# Power_Board_V3.net
KiCad netlist of a schematic drawn in EAGLE
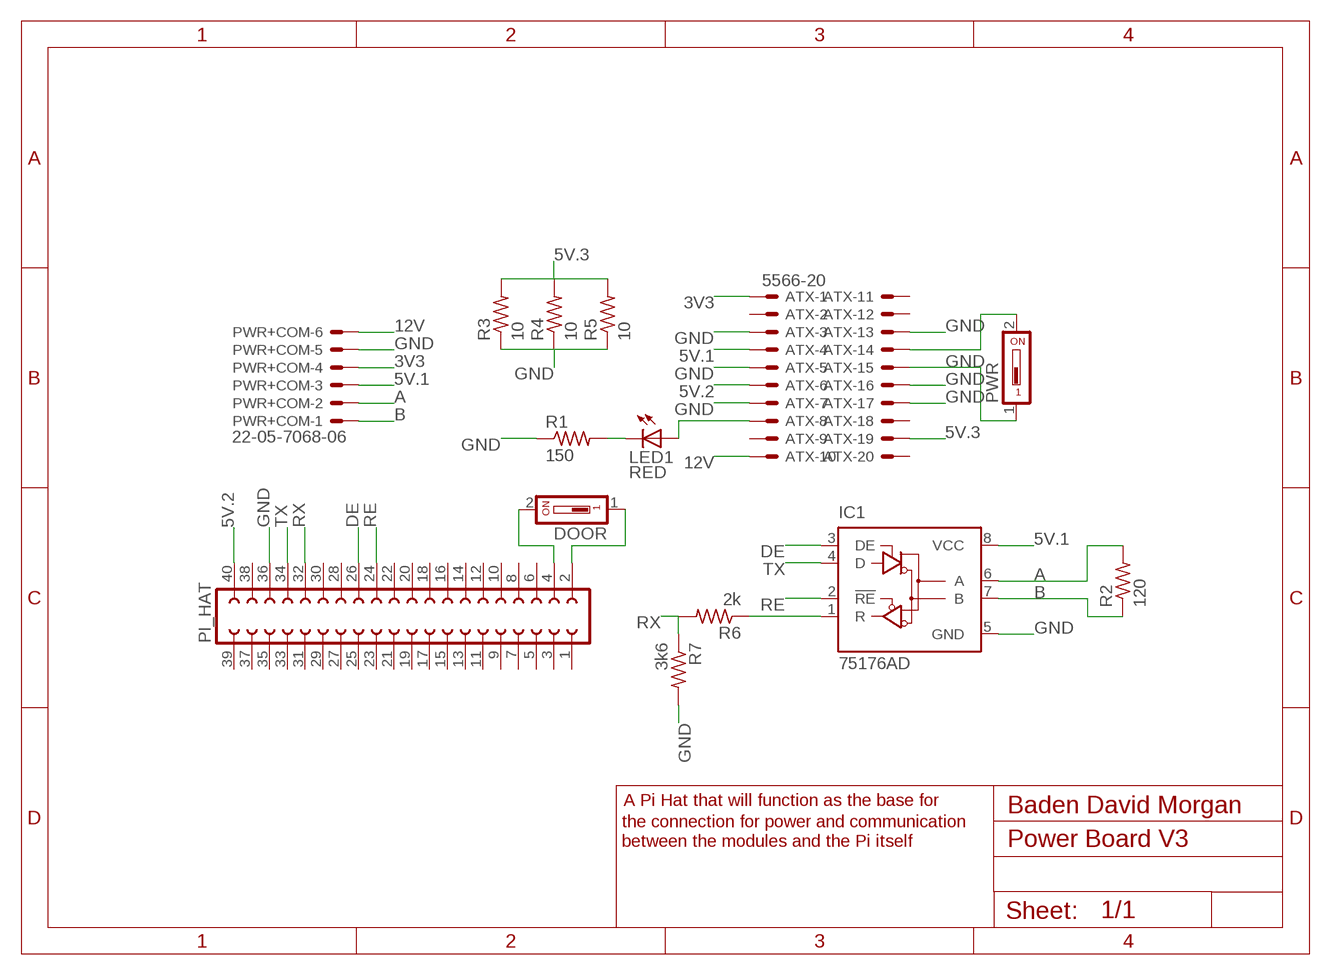
[diagram p0: schematic, sheet 1]

(export (version "E")
  (design (tool "Eeschema 10.0.6"))
  (components
    (comp (ref "ATX")
      (value "5566-20")
      (footprint "eagle-import:5566-20")
      (libsource (lib "eagle-import") (part "5566-20"))
    )
    (comp (ref "DOOR")
      (value "SD4-01")
      (footprint "eagle-import:SD4-01")
      (libsource (lib "eagle-import") (part "SD4-01"))
    )
    (comp (ref "IC1")
      (value "75176AD")
      (footprint "eagle-import:D_R-PDSO-G8")
      (libsource (lib "eagle-import") (part "75176AD"))
    )
    (comp (ref "LED1")
      (value "RED")
      (footprint "eagle-import:CHIPLED_1206")
      (libsource (lib "eagle-import") (part "LEDCHIPLED_1206"))
    )
    (comp (ref "PI_HAT")
      (value "FE20-2")
      (footprint "eagle-import:FE20-2")
      (libsource (lib "eagle-import") (part "FE20-2"))
    )
    (comp (ref "PWR")
      (value "SD4-01")
      (footprint "eagle-import:SD4-01")
      (libsource (lib "eagle-import") (part "SD4-01"))
    )
    (comp (ref "PWR+COM")
      (value "22-05-7068-06")
      (footprint "eagle-import:7395-06")
      (libsource (lib "eagle-import") (part "22-?-0605-7068"))
    )
    (comp (ref "R1")
      (value "150")
      (footprint "eagle-import:R0805")
      (libsource (lib "eagle-import") (part "resistor_R-US_R0805"))
    )
    (comp (ref "R2")
      (value "120")
      (footprint "eagle-import:R0805")
      (libsource (lib "eagle-import") (part "resistor_R-US_R0805"))
    )
    (comp (ref "R3")
      (value "10")
      (footprint "eagle-import:P0817V")
      (libsource (lib "eagle-import") (part "R-US_0817/7V"))
    )
    (comp (ref "R4")
      (value "10")
      (footprint "eagle-import:P0817V")
      (libsource (lib "eagle-import") (part "R-US_0817/7V"))
    )
    (comp (ref "R5")
      (value "10")
      (footprint "eagle-import:P0817V")
      (libsource (lib "eagle-import") (part "R-US_0817/7V"))
    )
    (comp (ref "R6")
      (value "2k")
      (footprint "eagle-import:R0805")
      (libsource (lib "eagle-import") (part "resistor_R-US_R0805"))
    )
    (comp (ref "R7")
      (value "3k6")
      (footprint "eagle-import:R0805")
      (libsource (lib "eagle-import") (part "resistor_R-US_R0805"))
    )
  )
  (nets
    (net (code "1") (name "/3V3") (class "Default")
      (node (ref "ATX") (pin "1") (pinfunction "S_1") (pintype "passive"))
      (node (ref "PWR+COM") (pin "4") (pinfunction "S_4") (pintype "passive"))
    )
    (net (code "2") (name "/5V.1") (class "Default")
      (node (ref "ATX") (pin "4") (pinfunction "S_4") (pintype "passive"))
      (node (ref "IC1") (pin "8") (pinfunction "VCC_8") (pintype "power_in"))
      (node (ref "PWR+COM") (pin "3") (pinfunction "S_3") (pintype "passive"))
    )
    (net (code "3") (name "/5V.2") (class "Default")
      (node (ref "ATX") (pin "6") (pinfunction "S_6") (pintype "passive"))
      (node (ref "PI_HAT") (pin "40") (pinfunction "40_40") (pintype "passive"))
    )
    (net (code "4") (name "/5V.3") (class "Default")
      (node (ref "ATX") (pin "19") (pinfunction "S_19") (pintype "passive"))
      (node (ref "R3") (pin "2") (pinfunction "2_2") (pintype "passive"))
      (node (ref "R4") (pin "2") (pinfunction "2_2") (pintype "passive"))
      (node (ref "R5") (pin "2") (pinfunction "2_2") (pintype "passive"))
    )
    (net (code "5") (name "/12V") (class "Default")
      (node (ref "ATX") (pin "10") (pinfunction "S_10") (pintype "passive"))
      (node (ref "PWR+COM") (pin "6") (pinfunction "S_6") (pintype "passive"))
    )
    (net (code "6") (name "/A") (class "Default")
      (node (ref "IC1") (pin "6") (pinfunction "A_6") (pintype "output"))
      (node (ref "PWR+COM") (pin "2") (pinfunction "S_2") (pintype "passive"))
      (node (ref "R2") (pin "2") (pinfunction "2_2") (pintype "passive"))
    )
    (net (code "7") (name "/B") (class "Default")
      (node (ref "IC1") (pin "7") (pinfunction "B_7") (pintype "output"))
      (node (ref "PWR+COM") (pin "1") (pinfunction "S_1") (pintype "passive"))
      (node (ref "R2") (pin "1") (pinfunction "1_1") (pintype "passive"))
    )
    (net (code "8") (name "/DE") (class "Default")
      (node (ref "IC1") (pin "3") (pinfunction "DE_3") (pintype "input"))
      (node (ref "PI_HAT") (pin "26") (pinfunction "26_26") (pintype "passive"))
    )
    (net (code "9") (name "/GND") (class "Default")
      (node (ref "ATX") (pin "13") (pinfunction "S_13") (pintype "passive"))
      (node (ref "ATX") (pin "15") (pinfunction "S_15") (pintype "passive"))
      (node (ref "ATX") (pin "16") (pinfunction "S_16") (pintype "passive"))
      (node (ref "ATX") (pin "17") (pinfunction "S_17") (pintype "passive"))
      (node (ref "ATX") (pin "3") (pinfunction "S_3") (pintype "passive"))
      (node (ref "ATX") (pin "5") (pinfunction "S_5") (pintype "passive"))
      (node (ref "ATX") (pin "7") (pinfunction "S_7") (pintype "passive"))
      (node (ref "IC1") (pin "5") (pinfunction "GND_5") (pintype "power_in"))
      (node (ref "PI_HAT") (pin "36") (pinfunction "36_36") (pintype "passive"))
      (node (ref "PWR") (pin "1") (pinfunction "1_1") (pintype "passive"))
      (node (ref "PWR+COM") (pin "5") (pinfunction "S_5") (pintype "passive"))
      (node (ref "R1") (pin "1") (pinfunction "1_1") (pintype "passive"))
      (node (ref "R3") (pin "1") (pinfunction "1_1") (pintype "passive"))
      (node (ref "R4") (pin "1") (pinfunction "1_1") (pintype "passive"))
      (node (ref "R5") (pin "1") (pinfunction "1_1") (pintype "passive"))
      (node (ref "R7") (pin "2") (pinfunction "2_2") (pintype "passive"))
    )
    (net (code "10") (name "/RE") (class "Default")
      (node (ref "IC1") (pin "2") (pinfunction "~{RE}_2") (pintype "input"))
      (node (ref "PI_HAT") (pin "24") (pinfunction "24_24") (pintype "passive"))
    )
    (net (code "11") (name "/RX") (class "Default")
      (node (ref "PI_HAT") (pin "32") (pinfunction "32_32") (pintype "passive"))
      (node (ref "R6") (pin "2") (pinfunction "2_2") (pintype "passive"))
      (node (ref "R7") (pin "1") (pinfunction "1_1") (pintype "passive"))
    )
    (net (code "12") (name "/TX") (class "Default")
      (node (ref "IC1") (pin "4") (pinfunction "D_4") (pintype "input"))
      (node (ref "PI_HAT") (pin "34") (pinfunction "34_34") (pintype "passive"))
    )
    (net (code "13") (name "Net-(ATXF-S)") (class "Default")
      (node (ref "ATX") (pin "14") (pinfunction "S_14") (pintype "passive"))
      (node (ref "PWR") (pin "2") (pinfunction "2_2") (pintype "passive"))
    )
    (net (code "14") (name "Net-(ATXS-S)") (class "Default")
      (node (ref "ATX") (pin "8") (pinfunction "S_8") (pintype "passive"))
      (node (ref "LED1") (pin "A") (pinfunction "A_A") (pintype "passive"))
    )
    (net (code "15") (name "Net-(DOOR-Pad1)") (class "Default")
      (node (ref "DOOR") (pin "1") (pinfunction "1_1") (pintype "passive"))
      (node (ref "PI_HAT") (pin "2") (pinfunction "2_2") (pintype "passive"))
    )
    (net (code "16") (name "Net-(DOOR-Pad2)") (class "Default")
      (node (ref "DOOR") (pin "2") (pinfunction "2_2") (pintype "passive"))
      (node (ref "PI_HAT") (pin "4") (pinfunction "4_4") (pintype "passive"))
    )
    (net (code "17") (name "Net-(IC1-R)") (class "Default")
      (node (ref "IC1") (pin "1") (pinfunction "R_1") (pintype "input"))
      (node (ref "R6") (pin "1") (pinfunction "1_1") (pintype "passive"))
    )
    (net (code "18") (name "Net-(LED1-PadC)") (class "Default")
      (node (ref "LED1") (pin "C") (pinfunction "C_C") (pintype "passive"))
      (node (ref "R1") (pin "2") (pinfunction "2_2") (pintype "passive"))
    )
    (net (code "19") (name "unconnected-(ATXC-S-Pad11)") (class "Default")
      (node (ref "ATX") (pin "11") (pinfunction "S_11") (pintype "passive"))
    )
    (net (code "20") (name "unconnected-(ATXD-S-Pad12)") (class "Default")
      (node (ref "ATX") (pin "12") (pinfunction "S_12") (pintype "passive"))
    )
    (net (code "21") (name "unconnected-(ATXJ-S-Pad18)") (class "Default")
      (node (ref "ATX") (pin "18") (pinfunction "S_18") (pintype "passive"))
    )
    (net (code "22") (name "unconnected-(ATXL-S-Pad2)") (class "Default")
      (node (ref "ATX") (pin "2") (pinfunction "S_2") (pintype "passive"))
    )
    (net (code "23") (name "unconnected-(ATXM-S-Pad20)") (class "Default")
      (node (ref "ATX") (pin "20") (pinfunction "S_20") (pintype "passive"))
    )
    (net (code "24") (name "unconnected-(ATXT-S-Pad9)") (class "Default")
      (node (ref "ATX") (pin "9") (pinfunction "S_9") (pintype "passive"))
    )
    (net (code "25") (name "unconnected-(PI_HAT-Pad1)") (class "Default")
      (node (ref "PI_HAT") (pin "1") (pinfunction "1_1") (pintype "passive"))
    )
    (net (code "26") (name "unconnected-(PI_HAT-Pad3)") (class "Default")
      (node (ref "PI_HAT") (pin "3") (pinfunction "3_3") (pintype "passive"))
    )
    (net (code "27") (name "unconnected-(PI_HAT-Pad5)") (class "Default")
      (node (ref "PI_HAT") (pin "5") (pinfunction "5_5") (pintype "passive"))
    )
    (net (code "28") (name "unconnected-(PI_HAT-Pad6)") (class "Default")
      (node (ref "PI_HAT") (pin "6") (pinfunction "6_6") (pintype "passive"))
    )
    (net (code "29") (name "unconnected-(PI_HAT-Pad7)") (class "Default")
      (node (ref "PI_HAT") (pin "7") (pinfunction "7_7") (pintype "passive"))
    )
    (net (code "30") (name "unconnected-(PI_HAT-Pad8)") (class "Default")
      (node (ref "PI_HAT") (pin "8") (pinfunction "8_8") (pintype "passive"))
    )
    (net (code "31") (name "unconnected-(PI_HAT-Pad9)") (class "Default")
      (node (ref "PI_HAT") (pin "9") (pinfunction "9_9") (pintype "passive"))
    )
    (net (code "32") (name "unconnected-(PI_HAT-Pad10)") (class "Default")
      (node (ref "PI_HAT") (pin "10") (pinfunction "10_10") (pintype "passive"))
    )
    (net (code "33") (name "unconnected-(PI_HAT-Pad11)") (class "Default")
      (node (ref "PI_HAT") (pin "11") (pinfunction "11_11") (pintype "passive"))
    )
    (net (code "34") (name "unconnected-(PI_HAT-Pad12)") (class "Default")
      (node (ref "PI_HAT") (pin "12") (pinfunction "12_12") (pintype "passive"))
    )
    (net (code "35") (name "unconnected-(PI_HAT-Pad13)") (class "Default")
      (node (ref "PI_HAT") (pin "13") (pinfunction "13_13") (pintype "passive"))
    )
    (net (code "36") (name "unconnected-(PI_HAT-Pad14)") (class "Default")
      (node (ref "PI_HAT") (pin "14") (pinfunction "14_14") (pintype "passive"))
    )
    (net (code "37") (name "unconnected-(PI_HAT-Pad15)") (class "Default")
      (node (ref "PI_HAT") (pin "15") (pinfunction "15_15") (pintype "passive"))
    )
    (net (code "38") (name "unconnected-(PI_HAT-Pad16)") (class "Default")
      (node (ref "PI_HAT") (pin "16") (pinfunction "16_16") (pintype "passive"))
    )
    (net (code "39") (name "unconnected-(PI_HAT-Pad17)") (class "Default")
      (node (ref "PI_HAT") (pin "17") (pinfunction "17_17") (pintype "passive"))
    )
    (net (code "40") (name "unconnected-(PI_HAT-Pad18)") (class "Default")
      (node (ref "PI_HAT") (pin "18") (pinfunction "18_18") (pintype "passive"))
    )
    (net (code "41") (name "unconnected-(PI_HAT-Pad19)") (class "Default")
      (node (ref "PI_HAT") (pin "19") (pinfunction "19_19") (pintype "passive"))
    )
    (net (code "42") (name "unconnected-(PI_HAT-Pad20)") (class "Default")
      (node (ref "PI_HAT") (pin "20") (pinfunction "20_20") (pintype "passive"))
    )
    (net (code "43") (name "unconnected-(PI_HAT-Pad21)") (class "Default")
      (node (ref "PI_HAT") (pin "21") (pinfunction "21_21") (pintype "passive"))
    )
    (net (code "44") (name "unconnected-(PI_HAT-Pad22)") (class "Default")
      (node (ref "PI_HAT") (pin "22") (pinfunction "22_22") (pintype "passive"))
    )
    (net (code "45") (name "unconnected-(PI_HAT-Pad23)") (class "Default")
      (node (ref "PI_HAT") (pin "23") (pinfunction "23_23") (pintype "passive"))
    )
    (net (code "46") (name "unconnected-(PI_HAT-Pad25)") (class "Default")
      (node (ref "PI_HAT") (pin "25") (pinfunction "25_25") (pintype "passive"))
    )
    (net (code "47") (name "unconnected-(PI_HAT-Pad27)") (class "Default")
      (node (ref "PI_HAT") (pin "27") (pinfunction "27_27") (pintype "passive"))
    )
    (net (code "48") (name "unconnected-(PI_HAT-Pad28)") (class "Default")
      (node (ref "PI_HAT") (pin "28") (pinfunction "28_28") (pintype "passive"))
    )
    (net (code "49") (name "unconnected-(PI_HAT-Pad29)") (class "Default")
      (node (ref "PI_HAT") (pin "29") (pinfunction "29_29") (pintype "passive"))
    )
    (net (code "50") (name "unconnected-(PI_HAT-Pad30)") (class "Default")
      (node (ref "PI_HAT") (pin "30") (pinfunction "30_30") (pintype "passive"))
    )
    (net (code "51") (name "unconnected-(PI_HAT-Pad31)") (class "Default")
      (node (ref "PI_HAT") (pin "31") (pinfunction "31_31") (pintype "passive"))
    )
    (net (code "52") (name "unconnected-(PI_HAT-Pad33)") (class "Default")
      (node (ref "PI_HAT") (pin "33") (pinfunction "33_33") (pintype "passive"))
    )
    (net (code "53") (name "unconnected-(PI_HAT-Pad35)") (class "Default")
      (node (ref "PI_HAT") (pin "35") (pinfunction "35_35") (pintype "passive"))
    )
    (net (code "54") (name "unconnected-(PI_HAT-Pad37)") (class "Default")
      (node (ref "PI_HAT") (pin "37") (pinfunction "37_37") (pintype "passive"))
    )
    (net (code "55") (name "unconnected-(PI_HAT-Pad38)") (class "Default")
      (node (ref "PI_HAT") (pin "38") (pinfunction "38_38") (pintype "passive"))
    )
    (net (code "56") (name "unconnected-(PI_HAT-Pad39)") (class "Default")
      (node (ref "PI_HAT") (pin "39") (pinfunction "39_39") (pintype "passive"))
    )
  )
)
